# BrakeStrobeLights.net
KiCad netlist of a schematic drawn in EAGLE
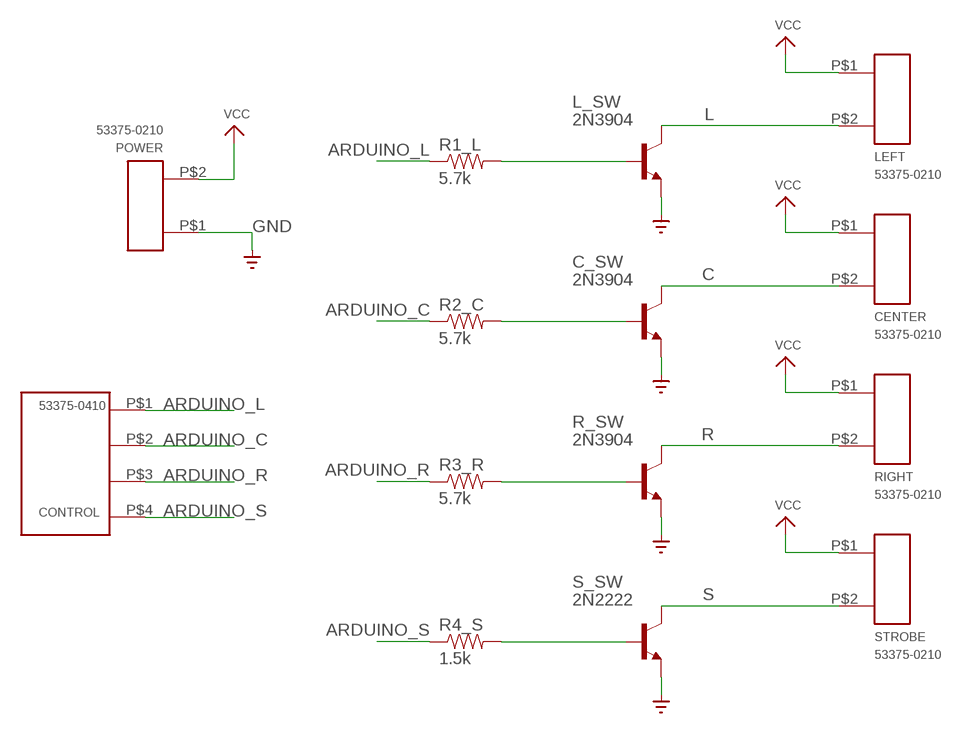
[diagram p0: schematic, sheet 1]

(export (version "E")
  (design (tool "Eeschema 10.0.6"))
  (components
    (comp (ref "CENTER")
      (value "53375-0210")
      (footprint "eagle-import:53375-0210-MINI-LOCK")
      (libsource (lib "eagle-import") (part "53375-0210"))
    )
    (comp (ref "CONTROL")
      (value "53375-0410")
      (footprint "eagle-import:53375-0410-MINI-LOCK")
      (libsource (lib "eagle-import") (part "53375-0410"))
    )
    (comp (ref "C_SW")
      (value "2N3904")
      (footprint "eagle-import:TO92")
      (libsource (lib "eagle-import") (part "2N3904"))
    )
    (comp (ref "LEFT")
      (value "53375-0210")
      (footprint "eagle-import:53375-0210-MINI-LOCK")
      (libsource (lib "eagle-import") (part "53375-0210"))
    )
    (comp (ref "L_SW")
      (value "2N3904")
      (footprint "eagle-import:TO92")
      (libsource (lib "eagle-import") (part "2N3904"))
    )
    (comp (ref "POWER")
      (value "53375-0210")
      (footprint "eagle-import:53375-0210-MINI-LOCK")
      (libsource (lib "eagle-import") (part "53375-0210"))
    )
    (comp (ref "R1_L")
      (value "5.7k")
      (footprint "eagle-import:1_6W-RES")
      (libsource (lib "eagle-import") (part "RESISTORPTH-1/6W"))
    )
    (comp (ref "R2_C")
      (value "5.7k")
      (footprint "eagle-import:1_6W-RES")
      (libsource (lib "eagle-import") (part "RESISTORPTH-1/6W"))
    )
    (comp (ref "R3_R")
      (value "5.7k")
      (footprint "eagle-import:1_6W-RES")
      (libsource (lib "eagle-import") (part "RESISTORPTH-1/6W"))
    )
    (comp (ref "R4_S")
      (value "1.5k")
      (footprint "eagle-import:1_6W-RES")
      (libsource (lib "eagle-import") (part "RESISTORPTH-1/6W"))
    )
    (comp (ref "RIGHT")
      (value "53375-0210")
      (footprint "eagle-import:53375-0210-MINI-LOCK")
      (libsource (lib "eagle-import") (part "53375-0210"))
    )
    (comp (ref "R_SW")
      (value "2N3904")
      (footprint "eagle-import:TO92")
      (libsource (lib "eagle-import") (part "2N3904"))
    )
    (comp (ref "STROBE")
      (value "53375-0210")
      (footprint "eagle-import:53375-0210-MINI-LOCK")
      (libsource (lib "eagle-import") (part "53375-0210"))
    )
    (comp (ref "S_SW")
      (value "2N2222")
      (footprint "eagle-import:TO92-EBC-OVAL")
      (libsource (lib "eagle-import") (part "2N2222"))
    )
  )
  (nets
    (net (code "1") (name "/ARDUINO_C") (class "Default")
      (node (ref "CONTROL") (pin "P$2") (pinfunction "2_P$2") (pintype "bidirectional"))
      (node (ref "R2_C") (pin "1") (pinfunction "1_1") (pintype "passive"))
    )
    (net (code "2") (name "/ARDUINO_L") (class "Default")
      (node (ref "CONTROL") (pin "P$1") (pinfunction "1_P$1") (pintype "bidirectional"))
      (node (ref "R1_L") (pin "1") (pinfunction "1_1") (pintype "passive"))
    )
    (net (code "3") (name "/ARDUINO_R") (class "Default")
      (node (ref "CONTROL") (pin "P$3") (pinfunction "3_P$3") (pintype "bidirectional"))
      (node (ref "R3_R") (pin "1") (pinfunction "1_1") (pintype "passive"))
    )
    (net (code "4") (name "/ARDUINO_S") (class "Default")
      (node (ref "CONTROL") (pin "P$4") (pinfunction "4_P$4") (pintype "bidirectional"))
      (node (ref "R4_S") (pin "1") (pinfunction "1_1") (pintype "passive"))
    )
    (net (code "5") (name "/C") (class "Default")
      (node (ref "CENTER") (pin "P$2") (pinfunction "2_P$2") (pintype "bidirectional"))
      (node (ref "C_SW") (pin "1") (pinfunction "C_1") (pintype "passive"))
    )
    (net (code "6") (name "/L") (class "Default")
      (node (ref "LEFT") (pin "P$2") (pinfunction "2_P$2") (pintype "bidirectional"))
      (node (ref "L_SW") (pin "1") (pinfunction "C_1") (pintype "passive"))
    )
    (net (code "7") (name "/R") (class "Default")
      (node (ref "RIGHT") (pin "P$2") (pinfunction "2_P$2") (pintype "bidirectional"))
      (node (ref "R_SW") (pin "1") (pinfunction "C_1") (pintype "passive"))
    )
    (net (code "8") (name "/S") (class "Default")
      (node (ref "STROBE") (pin "P$2") (pinfunction "2_P$2") (pintype "bidirectional"))
      (node (ref "S_SW") (pin "C") (pinfunction "C_C") (pintype "passive"))
    )
    (net (code "9") (name "GND_") (class "Default")
      (node (ref "C_SW") (pin "3") (pinfunction "E_3") (pintype "passive"))
      (node (ref "L_SW") (pin "3") (pinfunction "E_3") (pintype "passive"))
      (node (ref "POWER") (pin "P$1") (pinfunction "1_P$1") (pintype "bidirectional"))
      (node (ref "R_SW") (pin "3") (pinfunction "E_3") (pintype "passive"))
      (node (ref "S_SW") (pin "E") (pinfunction "E_E") (pintype "passive"))
    )
    (net (code "10") (name "Net-(C_SW-B)") (class "Default")
      (node (ref "C_SW") (pin "2") (pinfunction "B_2") (pintype "passive"))
      (node (ref "R2_C") (pin "2") (pinfunction "2_2") (pintype "passive"))
    )
    (net (code "11") (name "Net-(L_SW-B)") (class "Default")
      (node (ref "L_SW") (pin "2") (pinfunction "B_2") (pintype "passive"))
      (node (ref "R1_L") (pin "2") (pinfunction "2_2") (pintype "passive"))
    )
    (net (code "12") (name "Net-(R4_S-Pad2)") (class "Default")
      (node (ref "R4_S") (pin "2") (pinfunction "2_2") (pintype "passive"))
      (node (ref "S_SW") (pin "B") (pinfunction "B_B") (pintype "passive"))
    )
    (net (code "13") (name "Net-(R_SW-B)") (class "Default")
      (node (ref "R3_R") (pin "2") (pinfunction "2_2") (pintype "passive"))
      (node (ref "R_SW") (pin "2") (pinfunction "B_2") (pintype "passive"))
    )
    (net (code "14") (name "VCC") (class "Default")
      (node (ref "CENTER") (pin "P$1") (pinfunction "1_P$1") (pintype "bidirectional"))
      (node (ref "LEFT") (pin "P$1") (pinfunction "1_P$1") (pintype "bidirectional"))
      (node (ref "POWER") (pin "P$2") (pinfunction "2_P$2") (pintype "bidirectional"))
      (node (ref "RIGHT") (pin "P$1") (pinfunction "1_P$1") (pintype "bidirectional"))
      (node (ref "STROBE") (pin "P$1") (pinfunction "1_P$1") (pintype "bidirectional"))
    )
  )
)
